# ESP32.net
KiCad netlist of a schematic drawn in Altium Designer
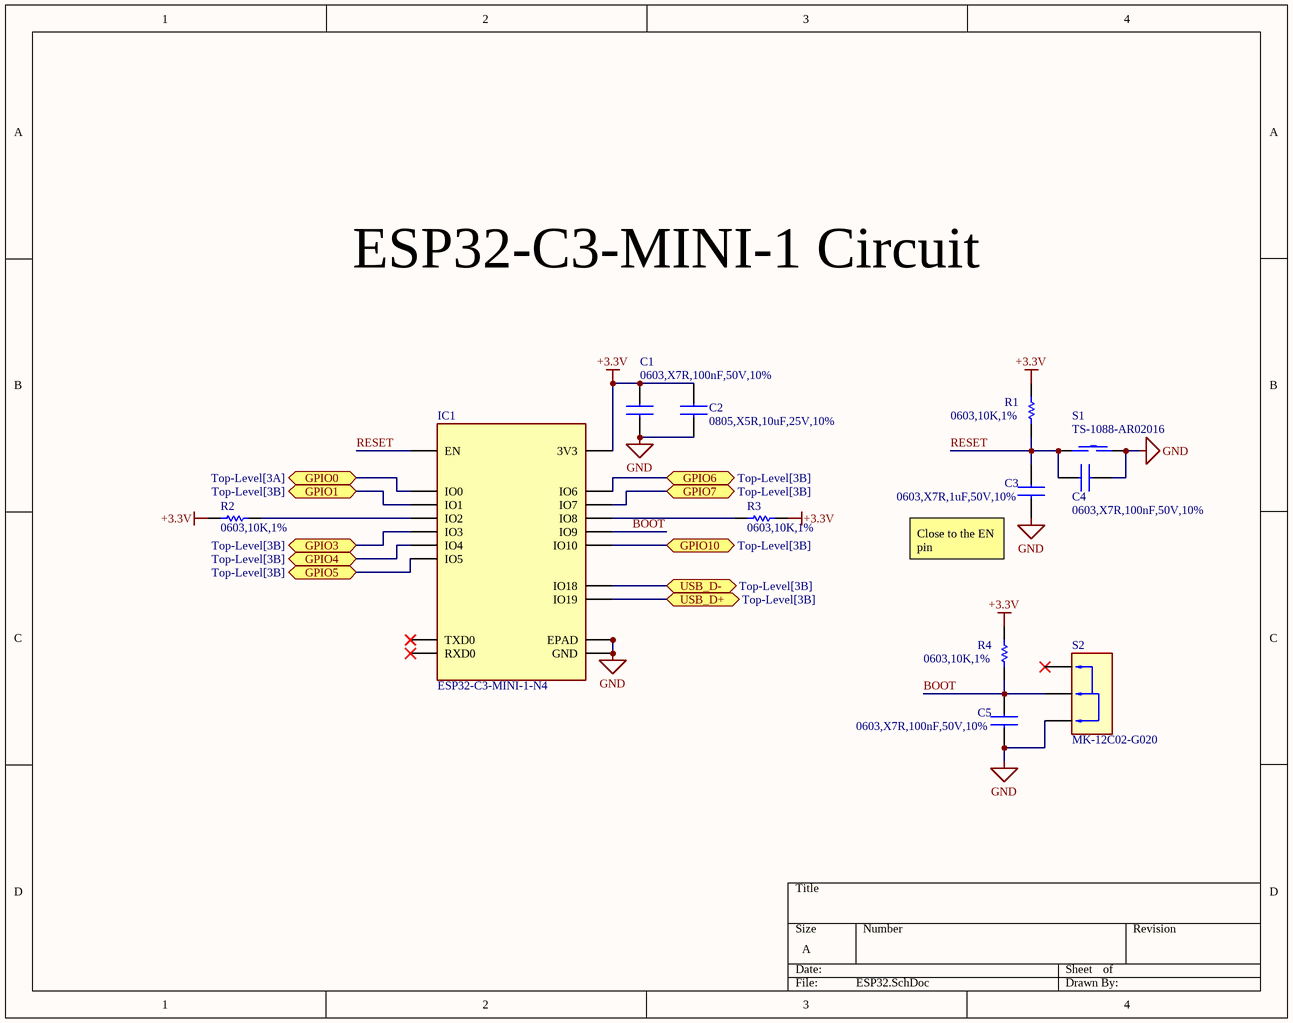
[diagram p0: ESP32.SchDoc]

(export (version "E")
  (design (tool "Eeschema 10.0.6"))
  (components
    (comp (ref "C1")
      (value "0603,X7R,100nF,50V,10%")
      (footprint "CAPC1608X90N")
      (description "50V 100nF X7R ±10% 0603 Multilayer Ceramic Capacitors MLCC - SMD/SMT ROHS")
      (fields
        (field (name "MANUFACTURER_PART_NUMBER") "CC0603KRX7R9BB104")
        (field (name "MOUSER PART NUMBER") "603-CC603KRX7R9BB104")
      )
      (libsource (lib "LC-SchLib") (part "CC0603KRX7R9BB104"))
    )
    (comp (ref "C2")
      (value "0805,X5R,10uF,25V,10%")
      (footprint "CAPC2012X145N")
      (description "10 µF ±10% 25V Ceramic Capacitor X5R 0805 (2012 Metric)")
      (fields
        (field (name "MANUFACTURER_PART_NUMBER") "CC0805KKX5R8BB106")
        (field (name "MOUSER PART NUMBER") "603-CC805KKX5R8BB106")
      )
      (libsource (lib "LC-SchLib") (part "CC0805KKX5R8BB106"))
    )
    (comp (ref "C3")
      (value "0603,X7R,1uF,50V,10%")
      (footprint "CAPC1608X90N")
      (description "50V 1uF X7R ±10% 0603 Multilayer Ceramic Capacitors MLCC - SMD/SMT ROHS")
      (fields
        (field (name "MANUFACTURER_PART_NUMBER") "CC0603KRX7R9BB105")
        (field (name "MOUSER PART NUMBER") "603-CC603KRX7R9BB105")
      )
      (libsource (lib "LC-SchLib") (part "CC0603KRX7R9BB105"))
    )
    (comp (ref "C4")
      (value "0603,X7R,100nF,50V,10%")
      (footprint "CAPC1608X90N")
      (description "50V 100nF X7R ±10% 0603 Multilayer Ceramic Capacitors MLCC - SMD/SMT ROHS")
      (fields
        (field (name "MANUFACTURER_PART_NUMBER") "CC0603KRX7R9BB104")
        (field (name "MOUSER PART NUMBER") "603-CC603KRX7R9BB104")
      )
      (libsource (lib "LC-SchLib") (part "CC0603KRX7R9BB104"))
    )
    (comp (ref "C5")
      (value "0603,X7R,100nF,50V,10%")
      (footprint "CAPC1608X90N")
      (description "50V 100nF X7R ±10% 0603 Multilayer Ceramic Capacitors MLCC - SMD/SMT ROHS")
      (fields
        (field (name "MANUFACTURER_PART_NUMBER") "CC0603KRX7R9BB104")
        (field (name "MOUSER PART NUMBER") "603-CC603KRX7R9BB104")
      )
      (libsource (lib "LC-SchLib") (part "CC0603KRX7R9BB104"))
    )
    (comp (ref "IC1")
      (value "ESP32-C3-MINI-1-N4")
      (footprint "ESP32C3MINI1N4")
      (fields
        (field (name "MOUSER PART NUMBER") "356-ESP32-C3-MINI1N4")
        (field (name "LCSC PART NUMBER") "C2838502")
      )
      (libsource (lib "LC-SchLib") (part "ESP32-C3-MINI-1-N4"))
    )
    (comp (ref "R1")
      (value "0603,10K,1%")
      (footprint "RESC1608X55N")
      (description "100mW Thick Film Resistor 75V ±100ppm/℃ ±1% 10kΩ 0603 Chip Resistor - Surface Mount ROHS")
      (fields
        (field (name "MANUFACTURER_PART_NUMBER") "RC0603FR-0710KL")
        (field (name "MOUSER PART NUMBER") "603-RC0603FR-0710KL")
      )
      (libsource (lib "LC-SchLib") (part "RC0603FR-0710KL"))
    )
    (comp (ref "R2")
      (value "0603,10K,1%")
      (footprint "RESC1608X55N")
      (description "100mW Thick Film Resistor 75V ±100ppm/℃ ±1% 10kΩ 0603 Chip Resistor - Surface Mount ROHS")
      (fields
        (field (name "MANUFACTURER_PART_NUMBER") "RC0603FR-0710KL")
        (field (name "MOUSER PART NUMBER") "603-RC0603FR-0710KL")
      )
      (libsource (lib "LC-SchLib") (part "RC0603FR-0710KL"))
    )
    (comp (ref "R3")
      (value "0603,10K,1%")
      (footprint "RESC1608X55N")
      (description "100mW Thick Film Resistor 75V ±100ppm/℃ ±1% 10kΩ 0603 Chip Resistor - Surface Mount ROHS")
      (fields
        (field (name "MANUFACTURER_PART_NUMBER") "RC0603FR-0710KL")
        (field (name "MOUSER PART NUMBER") "603-RC0603FR-0710KL")
      )
      (libsource (lib "LC-SchLib") (part "RC0603FR-0710KL"))
    )
    (comp (ref "R4")
      (value "0603,10K,1%")
      (footprint "RESC1608X55N")
      (description "100mW Thick Film Resistor 75V ±100ppm/℃ ±1% 10kΩ 0603 Chip Resistor - Surface Mount ROHS")
      (fields
        (field (name "MANUFACTURER_PART_NUMBER") "RC0603FR-0710KL")
        (field (name "MOUSER PART NUMBER") "603-RC0603FR-0710KL")
      )
      (libsource (lib "LC-SchLib") (part "RC0603FR-0710KL"))
    )
    (comp (ref "S1")
      (value "TS-1088-AR02016")
      (footprint "SW-SMD_L3.9-W3.0-P4.45")
      (fields (field (name "LCSC PART NUMBER") "C720477"))
      (libsource (lib "LC-SchLib") (part "TS-1088-AR02016"))
    )
    (comp (ref "S2")
      (value "MK-12C02-G020")
      (footprint "SW-SMD_MK-12C02-G020")
      (description "Surface Mount, Right Angle 1A SPDT 6V Black 10,000 Cycles SMD Slide Switches ROHS")
      (fields (field (name "LCSC PART NUMBER") "C963206"))
      (libsource (lib "LC-SchLib") (part "MK-12C02-G020"))
    )
  )
  (nets
    (net (code "1") (name "+3.3V") (class "Default")
      (node (ref "C1") (pin "2") (pinfunction "2_2") (pintype "passive"))
      (node (ref "C2") (pin "2") (pinfunction "2_2") (pintype "passive"))
      (node (ref "IC1") (pin "3") (pinfunction "3V3_3") (pintype "passive"))
      (node (ref "R1") (pin "2") (pinfunction "2_2") (pintype "passive"))
      (node (ref "R2") (pin "2") (pinfunction "2_2") (pintype "passive"))
      (node (ref "R3") (pin "2") (pinfunction "2_2") (pintype "passive"))
      (node (ref "R4") (pin "2") (pinfunction "2_2") (pintype "passive"))
    )
    (net (code "2") (name "/BOOT") (class "Default")
      (node (ref "C5") (pin "1") (pinfunction "1_1") (pintype "passive"))
      (node (ref "IC1") (pin "23") (pinfunction "IO9_23") (pintype "passive"))
      (node (ref "R4") (pin "1") (pinfunction "1_1") (pintype "passive"))
      (node (ref "S2") (pin "2") (pinfunction "2_2") (pintype "passive"))
    )
    (net (code "3") (name "/GPIO0") (class "Default")
      (node (ref "IC1") (pin "12") (pinfunction "IO0_12") (pintype "passive"))
    )
    (net (code "4") (name "/GPIO1") (class "Default")
      (node (ref "IC1") (pin "13") (pinfunction "IO1_13") (pintype "passive"))
    )
    (net (code "5") (name "/GPIO3") (class "Default")
      (node (ref "IC1") (pin "6") (pinfunction "IO3_6") (pintype "passive"))
    )
    (net (code "6") (name "/GPIO4") (class "Default")
      (node (ref "IC1") (pin "18") (pinfunction "IO4_18") (pintype "passive"))
    )
    (net (code "7") (name "/GPIO5") (class "Default")
      (node (ref "IC1") (pin "19") (pinfunction "IO5_19") (pintype "passive"))
    )
    (net (code "8") (name "/GPIO6") (class "Default")
      (node (ref "IC1") (pin "20") (pinfunction "IO6_20") (pintype "passive"))
    )
    (net (code "9") (name "/GPIO7") (class "Default")
      (node (ref "IC1") (pin "21") (pinfunction "IO7_21") (pintype "passive"))
    )
    (net (code "10") (name "/GPIO10") (class "Default")
      (node (ref "IC1") (pin "16") (pinfunction "IO10_16") (pintype "passive"))
    )
    (net (code "11") (name "/RESET") (class "Default")
      (node (ref "C3") (pin "2") (pinfunction "2_2") (pintype "passive"))
      (node (ref "C4") (pin "2") (pinfunction "2_2") (pintype "passive"))
      (node (ref "IC1") (pin "8") (pinfunction "EN_8") (pintype "passive"))
      (node (ref "R1") (pin "1") (pinfunction "1_1") (pintype "passive"))
      (node (ref "S1") (pin "2") (pinfunction "2_2") (pintype "passive"))
    )
    (net (code "12") (name "/USB_D+") (class "Default")
      (node (ref "IC1") (pin "27") (pinfunction "IO19_27") (pintype "passive"))
    )
    (net (code "13") (name "/USB_D-") (class "Default")
      (node (ref "IC1") (pin "26") (pinfunction "IO18_26") (pintype "passive"))
    )
    (net (code "14") (name "GND") (class "Default")
      (node (ref "C1") (pin "1") (pinfunction "1_1") (pintype "passive"))
      (node (ref "C2") (pin "1") (pinfunction "1_1") (pintype "passive"))
      (node (ref "C3") (pin "1") (pinfunction "1_1") (pintype "passive"))
      (node (ref "C4") (pin "1") (pinfunction "1_1") (pintype "passive"))
      (node (ref "C5") (pin "2") (pinfunction "2_2") (pintype "passive"))
      (node (ref "IC1") (pin "1") (pinfunction "GND_1") (pintype "passive"))
      (node (ref "IC1") (pin "11") (pinfunction "GND_11") (pintype "passive"))
      (node (ref "IC1") (pin "14") (pinfunction "GND_14") (pintype "passive"))
      (node (ref "IC1") (pin "2") (pinfunction "GND_2") (pintype "passive"))
      (node (ref "IC1") (pin "36") (pinfunction "GND_36") (pintype "passive"))
      (node (ref "IC1") (pin "37") (pinfunction "GND_37") (pintype "passive"))
      (node (ref "IC1") (pin "38") (pinfunction "GND_38") (pintype "passive"))
      (node (ref "IC1") (pin "39") (pinfunction "GND_39") (pintype "passive"))
      (node (ref "IC1") (pin "40") (pinfunction "GND_40") (pintype "passive"))
      (node (ref "IC1") (pin "41") (pinfunction "GND_41") (pintype "passive"))
      (node (ref "IC1") (pin "42") (pinfunction "GND_42") (pintype "passive"))
      (node (ref "IC1") (pin "43") (pinfunction "GND_43") (pintype "passive"))
      (node (ref "IC1") (pin "44") (pinfunction "GND_44") (pintype "passive"))
      (node (ref "IC1") (pin "45") (pinfunction "GND_45") (pintype "passive"))
      (node (ref "IC1") (pin "46") (pinfunction "GND_46") (pintype "passive"))
      (node (ref "IC1") (pin "47") (pinfunction "GND_47") (pintype "passive"))
      (node (ref "IC1") (pin "48") (pinfunction "GND_48") (pintype "passive"))
      (node (ref "IC1") (pin "49") (pinfunction "EPAD_49") (pintype "passive"))
      (node (ref "IC1") (pin "50") (pinfunction "EPAD_50") (pintype "passive"))
      (node (ref "IC1") (pin "51") (pinfunction "EPAD_51") (pintype "passive"))
      (node (ref "IC1") (pin "52") (pinfunction "EPAD_52") (pintype "passive"))
      (node (ref "IC1") (pin "53") (pinfunction "EPAD_53") (pintype "passive"))
      (node (ref "IC1") (pin "54") (pinfunction "EPAD_54") (pintype "passive"))
      (node (ref "IC1") (pin "55") (pinfunction "EPAD_55") (pintype "passive"))
      (node (ref "IC1") (pin "56") (pinfunction "EPAD_56") (pintype "passive"))
      (node (ref "IC1") (pin "57") (pinfunction "EPAD_57") (pintype "passive"))
      (node (ref "IC1") (pin "58") (pinfunction "GND_58") (pintype "passive"))
      (node (ref "IC1") (pin "59") (pinfunction "GND_59") (pintype "passive"))
      (node (ref "IC1") (pin "60") (pinfunction "GND_60") (pintype "passive"))
      (node (ref "IC1") (pin "61") (pinfunction "GND_61") (pintype "passive"))
      (node (ref "S1") (pin "1") (pinfunction "1_1") (pintype "passive"))
      (node (ref "S2") (pin "3") (pinfunction "3_3") (pintype "passive"))
    )
    (net (code "15") (name "Net-(IC1-IO2)") (class "Default")
      (node (ref "IC1") (pin "5") (pinfunction "IO2_5") (pintype "passive"))
      (node (ref "R2") (pin "1") (pinfunction "1_1") (pintype "passive"))
    )
    (net (code "16") (name "Net-(IC1-IO8)") (class "Default")
      (node (ref "IC1") (pin "22") (pinfunction "IO8_22") (pintype "passive"))
      (node (ref "R3") (pin "1") (pinfunction "1_1") (pintype "passive"))
    )
    (net (code "17") (name "unconnected-(IC1-RXD0-Pad30)") (class "Default")
      (node (ref "IC1") (pin "30") (pinfunction "RXD0_30") (pintype "passive+no_connect"))
    )
    (net (code "18") (name "unconnected-(IC1-TXD0-Pad31)") (class "Default")
      (node (ref "IC1") (pin "31") (pinfunction "TXD0_31") (pintype "passive+no_connect"))
    )
    (net (code "19") (name "unconnected-(S2-Pad1)") (class "Default")
      (node (ref "S2") (pin "1") (pinfunction "1_1") (pintype "passive+no_connect"))
    )
  )
)
